# LED.net
KiCad netlist of a schematic drawn in Altium Designer
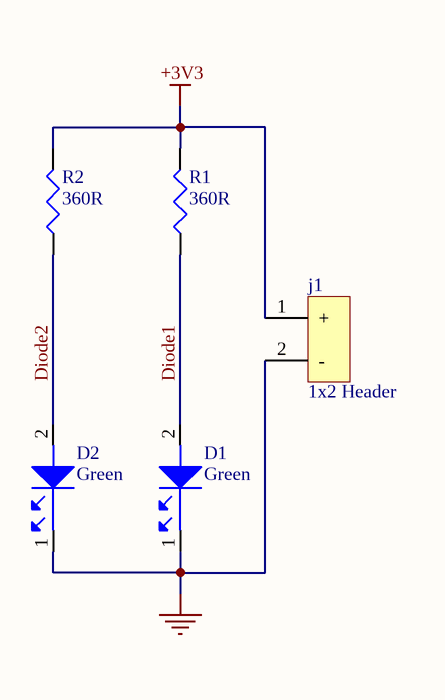
[diagram p0: LED.SchDoc]

(export (version "E")
  (design (tool "Eeschema 10.0.6"))
  (components
    (comp (ref "D1")
      (value "Green")
      (footprint "LED0603_G")
      (description "LED GREEN 0603 SMD")
      (fields
        (field (name "MANUFACTURER") "Panasonic SSG")
        (field (name "MANUFACTURER PART NUMBER") "LNJ337W83RA")
      )
      (libsource (lib "LED_SchLib") (part "LNJ337W83RA"))
    )
    (comp (ref "D2")
      (value "Green")
      (footprint "LED0603_G")
      (description "LED GREEN 0603 SMD")
      (fields
        (field (name "MANUFACTURER") "Panasonic SSG")
        (field (name "MANUFACTURER PART NUMBER") "LNJ337W83RA")
      )
      (libsource (lib "LED_SchLib") (part "LNJ337W83RA"))
    )
    (comp (ref "j1")
      (value "1x2 Header")
      (footprint "HDR1X2")
      (description "KK 254 Wire-to-Board Header, Vertical, with Friction Lock, 2 Circuits, Gold (Au) Plating")
      (fields (field (name "MANUFACTURER") "Molex") (field (name "MANUFACTURER PART NUMBER") "22-29-2021"))
      (libsource (lib "LED_SchLib") (part "22-29-2021"))
    )
    (comp (ref "R1")
      (value "360R")
      (footprint "R0805")
      (description "Res Thick Film 0805 360 Ohm 1% 1/8W ±100ppm/°C Molded SMD SMD Paper T/R")
      (fields
        (field (name "MANUFACTURER") "Vishay")
        (field (name "MANUFACTURER PART NUMBER") "CRCW0805360RFKEA")
      )
      (libsource (lib "LED_SchLib") (part "CRCW0805360RFKEA"))
    )
    (comp (ref "R2")
      (value "360R")
      (footprint "R0805")
      (description "Res Thick Film 0805 360 Ohm 1% 1/8W ±100ppm/°C Molded SMD SMD Paper T/R")
      (fields
        (field (name "MANUFACTURER") "Vishay")
        (field (name "MANUFACTURER PART NUMBER") "CRCW0805360RFKEA")
      )
      (libsource (lib "LED_SchLib") (part "CRCW0805360RFKEA"))
    )
  )
  (nets
    (net (code "1") (name "+3V3") (class "Default")
      (node (ref "R1") (pin "2") (pinfunction "2_2") (pintype "passive"))
      (node (ref "R2") (pin "2") (pinfunction "2_2") (pintype "passive"))
      (node (ref "j1") (pin "1") (pinfunction "+_1") (pintype "passive"))
    )
    (net (code "2") (name "/Diode1") (class "Default")
      (node (ref "D1") (pin "2") (pinfunction "2_2") (pintype "passive"))
      (node (ref "R1") (pin "1") (pinfunction "1_1") (pintype "passive"))
    )
    (net (code "3") (name "/Diode2") (class "Default")
      (node (ref "D2") (pin "2") (pinfunction "2_2") (pintype "passive"))
      (node (ref "R2") (pin "1") (pinfunction "1_1") (pintype "passive"))
    )
    (net (code "4") (name "GND") (class "Default")
      (node (ref "D1") (pin "1") (pinfunction "1_1") (pintype "passive"))
      (node (ref "D2") (pin "1") (pinfunction "1_1") (pintype "passive"))
      (node (ref "j1") (pin "2") (pinfunction "-_2") (pintype "passive"))
    )
  )
)
